# ConverterSch_2ndDriver.net
KiCad netlist of a schematic drawn in Altium Designer
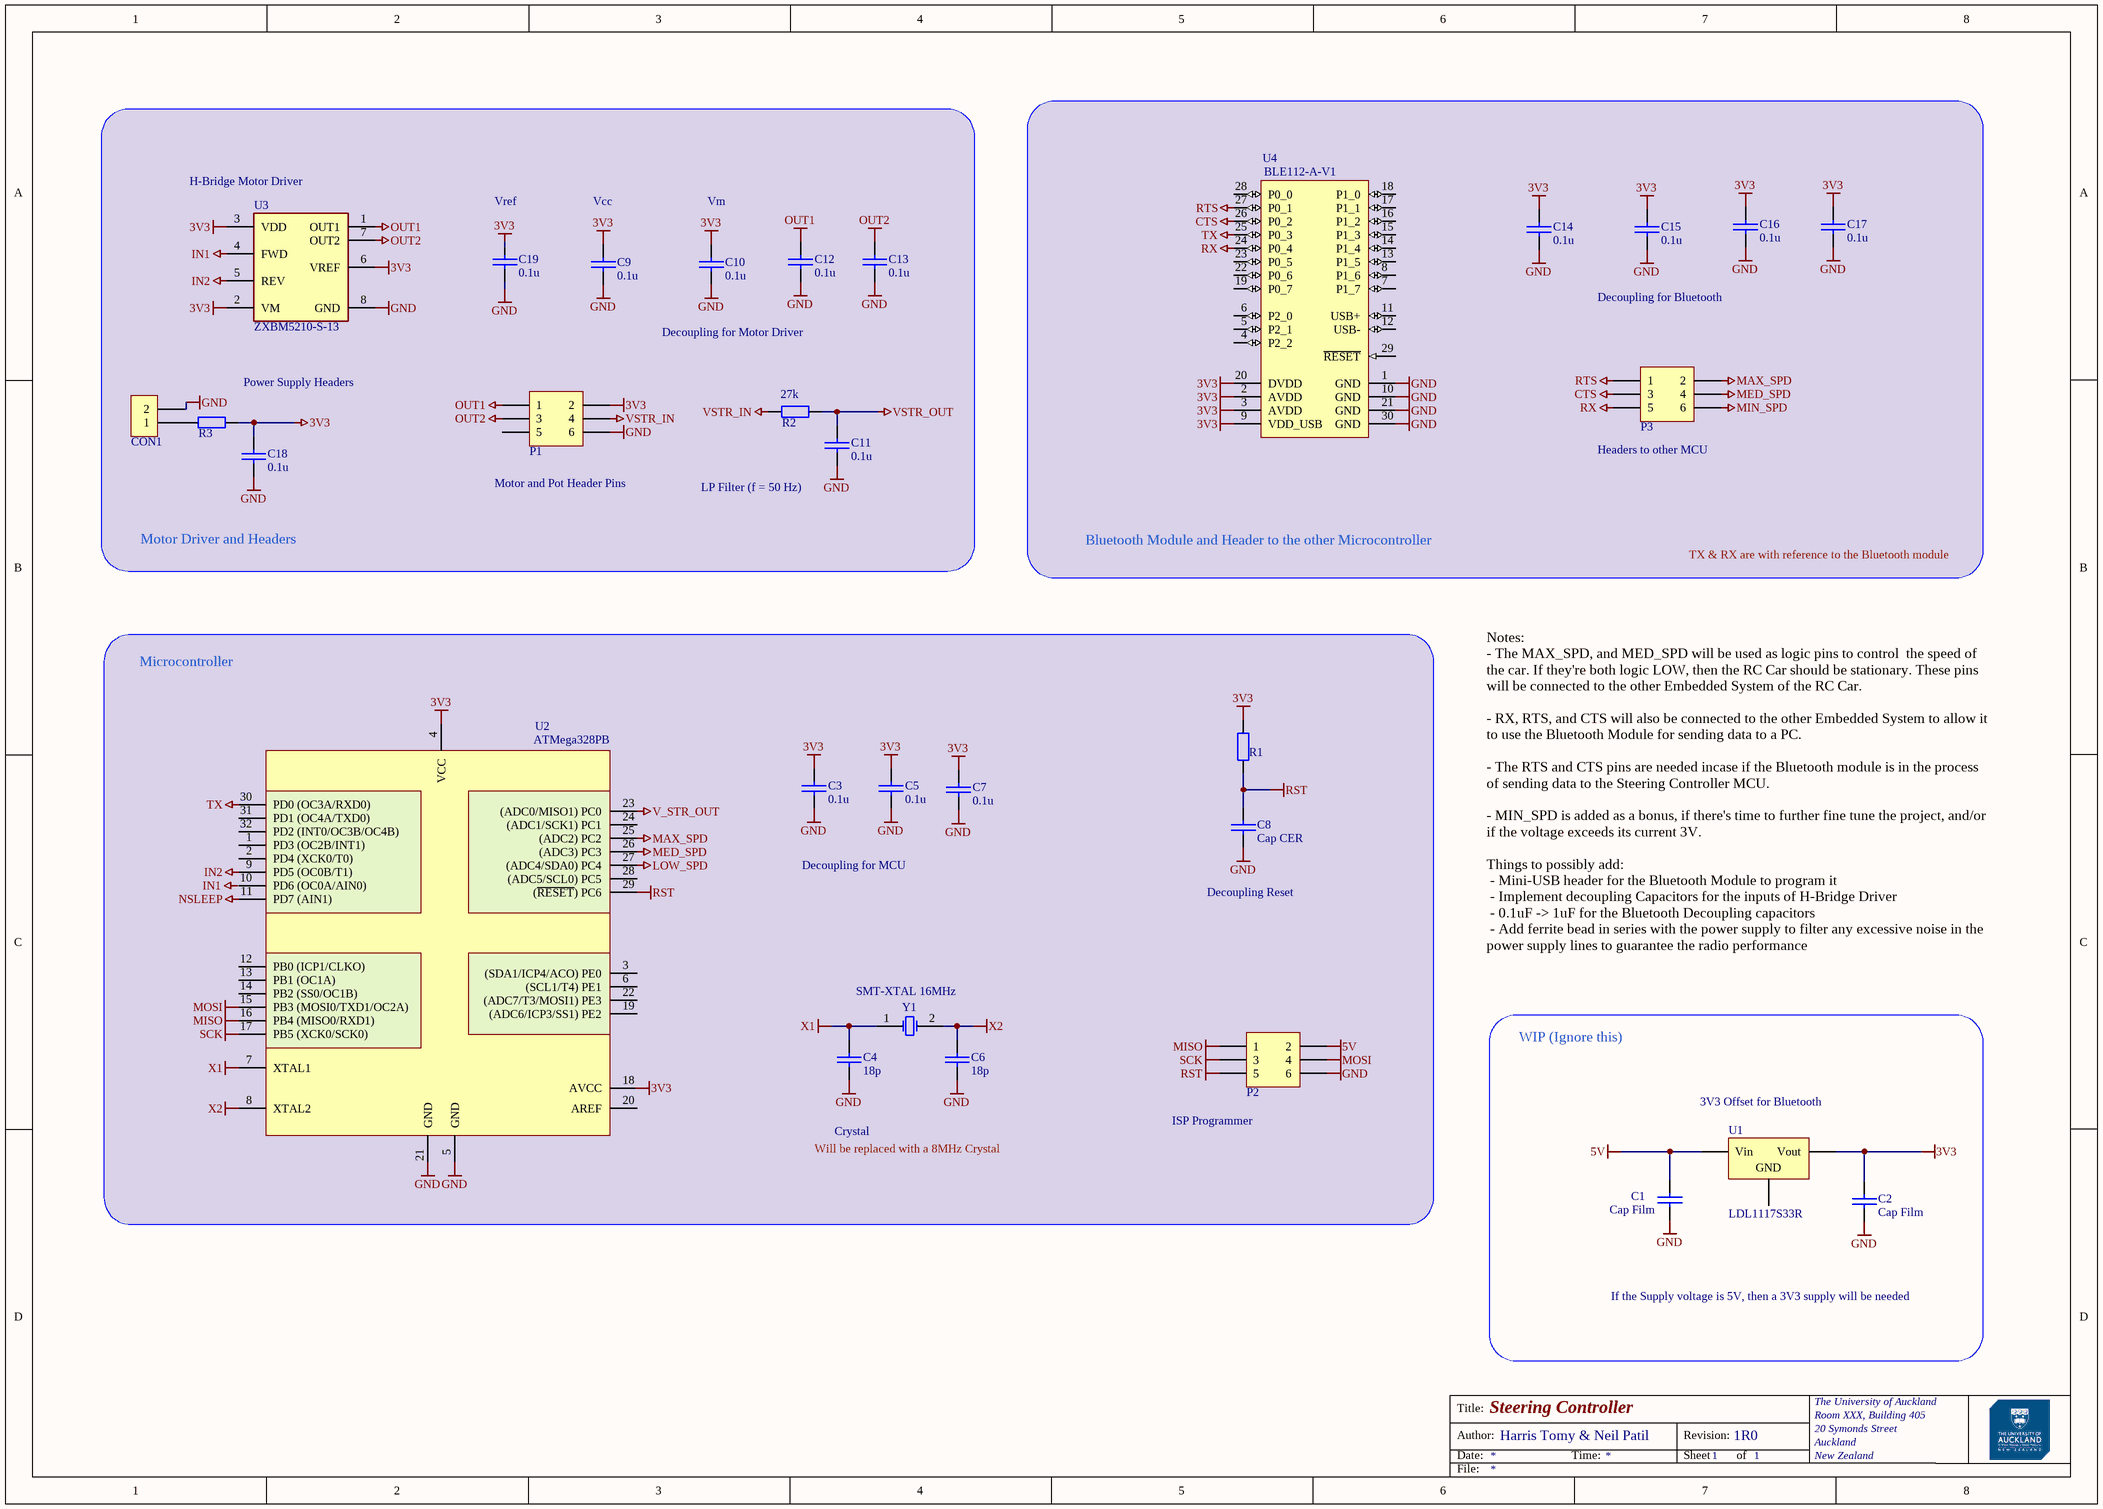
[diagram p0: ConverterSch_2ndDriver.SchDoc]

(export (version "E")
  (design (tool "Eeschema 10.0.6"))
  (components
    (comp (ref "C1")
      (value "Cap Film")
      (footprint "LDECE4150KA0N00")
      (description "CAP FILM 1.5UF 10% 50VDC 2824")
      (fields (field (name "MPN") "LDECE4150KA0N00") (field (name "MANUFACTURER") "KEMET"))
      (libsource (lib "E209_Lib") (part "Cap Film SMD LDECE4150KA0N00"))
    )
    (comp (ref "C2")
      (value "Cap Film")
      (footprint "LDECE4150KA0N00")
      (description "CAP FILM 1.5UF 10% 50VDC 2824")
      (fields (field (name "MPN") "LDECE4150KA0N00") (field (name "MANUFACTURER") "KEMET"))
      (libsource (lib "E209_Lib") (part "Cap Film SMD LDECE4150KA0N00"))
    )
    (comp (ref "C3")
      (value "0.1u")
      (footprint "C1206")
      (description "CAP CER 0.1UF 100V C0G 1206")
      (fields (field (name "MPN") "C3216C0G2A104J160AC") (field (name "MANUFACTURER") "TDK Corporation"))
      (libsource (lib "E209_Lib") (part "Cap CER Decoup C3216C0G2A104J160AC"))
    )
    (comp (ref "C4")
      (value "18p")
      (footprint "C1206")
      (description "CAP CER 0.1UF 100V C0G 1206")
      (fields (field (name "MPN") "C3216C0G2A104J160AC") (field (name "MANUFACTURER") "TDK Corporation"))
      (libsource (lib "E209_Lib") (part "Cap CER Decoup C3216C0G2A104J160AC"))
    )
    (comp (ref "C5")
      (value "0.1u")
      (footprint "C1206")
      (description "CAP CER 0.1UF 100V C0G 1206")
      (fields (field (name "MPN") "C3216C0G2A104J160AC") (field (name "MANUFACTURER") "TDK Corporation"))
      (libsource (lib "E209_Lib") (part "Cap CER Decoup C3216C0G2A104J160AC"))
    )
    (comp (ref "C6")
      (value "18p")
      (footprint "C1206")
      (description "CAP CER 0.1UF 100V C0G 1206")
      (fields (field (name "MPN") "C3216C0G2A104J160AC") (field (name "MANUFACTURER") "TDK Corporation"))
      (libsource (lib "E209_Lib") (part "Cap CER Decoup C3216C0G2A104J160AC"))
    )
    (comp (ref "C7")
      (value "0.1u")
      (footprint "C1206")
      (description "CAP CER 0.1UF 100V C0G 1206")
      (fields (field (name "MPN") "C3216C0G2A104J160AC") (field (name "MANUFACTURER") "TDK Corporation"))
      (libsource (lib "E209_Lib") (part "Cap CER Decoup C3216C0G2A104J160AC"))
    )
    (comp (ref "C8")
      (value "Cap CER")
      (footprint "C1206")
      (description "CAP CER 0.1UF 100V C0G 1206")
      (fields (field (name "MPN") "C3216C0G2A104J160AC") (field (name "MANUFACTURER") "TDK Corporation"))
      (libsource (lib "E209_Lib") (part "Cap CER Decoup C3216C0G2A104J160AC"))
    )
    (comp (ref "C9")
      (value "0.1u")
      (footprint "C1206")
      (description "CAP CER 0.1UF 100V C0G 1206")
      (fields (field (name "MPN") "C3216C0G2A104J160AC") (field (name "MANUFACTURER") "TDK Corporation"))
      (libsource (lib "E209_Lib") (part "Cap CER Decoup C3216C0G2A104J160AC"))
    )
    (comp (ref "C10")
      (value "0.1u")
      (footprint "C1206")
      (description "CAP CER 0.1UF 100V C0G 1206")
      (fields (field (name "MPN") "C3216C0G2A104J160AC") (field (name "MANUFACTURER") "TDK Corporation"))
      (libsource (lib "E209_Lib") (part "Cap CER Decoup C3216C0G2A104J160AC"))
    )
    (comp (ref "C11")
      (value "0.1u")
      (footprint "C1206")
      (description "CAP CER 0.1UF 100V C0G 1206")
      (fields (field (name "MPN") "C3216C0G2A104J160AC") (field (name "MANUFACTURER") "TDK Corporation"))
      (libsource (lib "E209_Lib") (part "Cap CER Decoup C3216C0G2A104J160AC"))
    )
    (comp (ref "C12")
      (value "0.1u")
      (footprint "C1206")
      (description "CAP CER 0.1UF 100V C0G 1206")
      (fields (field (name "MPN") "C3216C0G2A104J160AC") (field (name "MANUFACTURER") "TDK Corporation"))
      (libsource (lib "E209_Lib") (part "Cap CER Decoup C3216C0G2A104J160AC"))
    )
    (comp (ref "C13")
      (value "0.1u")
      (footprint "C1206")
      (description "CAP CER 0.1UF 100V C0G 1206")
      (fields (field (name "MPN") "C3216C0G2A104J160AC") (field (name "MANUFACTURER") "TDK Corporation"))
      (libsource (lib "E209_Lib") (part "Cap CER Decoup C3216C0G2A104J160AC"))
    )
    (comp (ref "C14")
      (value "0.1u")
      (footprint "C1206")
      (description "CAP CER 0.1UF 100V C0G 1206")
      (fields (field (name "MPN") "C3216C0G2A104J160AC") (field (name "MANUFACTURER") "TDK Corporation"))
      (libsource (lib "E209_Lib") (part "Cap CER Decoup C3216C0G2A104J160AC"))
    )
    (comp (ref "C15")
      (value "0.1u")
      (footprint "C1206")
      (description "CAP CER 0.1UF 100V C0G 1206")
      (fields (field (name "MPN") "C3216C0G2A104J160AC") (field (name "MANUFACTURER") "TDK Corporation"))
      (libsource (lib "E209_Lib") (part "Cap CER Decoup C3216C0G2A104J160AC"))
    )
    (comp (ref "C16")
      (value "0.1u")
      (footprint "C1206")
      (description "CAP CER 0.1UF 100V C0G 1206")
      (fields (field (name "MPN") "C3216C0G2A104J160AC") (field (name "MANUFACTURER") "TDK Corporation"))
      (libsource (lib "E209_Lib") (part "Cap CER Decoup C3216C0G2A104J160AC"))
    )
    (comp (ref "C17")
      (value "0.1u")
      (footprint "C1206")
      (description "CAP CER 0.1UF 100V C0G 1206")
      (fields (field (name "MPN") "C3216C0G2A104J160AC") (field (name "MANUFACTURER") "TDK Corporation"))
      (libsource (lib "E209_Lib") (part "Cap CER Decoup C3216C0G2A104J160AC"))
    )
    (comp (ref "C18")
      (value "0.1u")
      (footprint "C1206")
      (description "CAP CER 0.1UF 100V C0G 1206")
      (fields (field (name "MPN") "C3216C0G2A104J160AC") (field (name "MANUFACTURER") "TDK Corporation"))
      (libsource (lib "E209_Lib") (part "Cap CER Decoup C3216C0G2A104J160AC"))
    )
    (comp (ref "C19")
      (value "0.1u")
      (footprint "C1206")
      (description "CAP CER 0.1UF 100V C0G 1206")
      (fields (field (name "MPN") "C3216C0G2A104J160AC") (field (name "MANUFACTURER") "TDK Corporation"))
      (libsource (lib "E209_Lib") (part "Cap CER Decoup C3216C0G2A104J160AC"))
    )
    (comp (ref "CON1")
      (value "Header 2X1")
      (footprint "HDR2X1_2P54")
      (libsource (lib "CommonDevices_V1") (part "HDR2X1"))
    )
    (comp (ref "P1")
      (value "HDR3X2")
      (footprint "HDR2X3_2P54")
      (description "Header, 3-Pin, Dual row")
      (libsource (lib "CommonDevices_V1") (part "HDR3X2"))
    )
    (comp (ref "P2")
      (value "HDR3X2")
      (footprint "HDR2X3_2P54")
      (description "Header, 3-Pin, Dual row")
      (libsource (lib "CommonDevices_V1") (part "HDR3X2"))
    )
    (comp (ref "P3")
      (value "HDR3X2")
      (footprint "HDR2X3_2P54")
      (description "Header, 3-Pin, Dual row")
      (libsource (lib "CommonDevices_V1") (part "HDR3X2"))
    )
    (comp (ref "R1")
      (value "Resistor 1206")
      (footprint "R1206")
      (description "RES1206")
      (fields (field (name "MPN") "?"))
      (libsource (lib "E209_Lib") (part "RES1206"))
    )
    (comp (ref "R2")
      (value "Resistor 0805")
      (footprint "R0805")
      (description "RES0805")
      (fields (field (name "MPN") "?"))
      (libsource (lib "E209_Lib") (part "RES0805"))
    )
    (comp (ref "R3")
      (value "Resistor 0805")
      (footprint "R0805")
      (description "RES0805")
      (fields (field (name "MPN") "?"))
      (libsource (lib "E209_Lib") (part "RES0805"))
    )
    (comp (ref "U1")
      (value "LDL1117S33R")
      (footprint "SOT223L")
      (description "IC REG LINEAR 3.3V 1.2A SOT223")
      (fields (field (name "MANUFACTURER") "STMicroelectronics"))
      (libsource (lib "E209_Lib") (part "LDO LDL1117S33R"))
    )
    (comp (ref "U2")
      (value "ATMega328PB")
      (footprint "TQFP32")
      (description "IC MCU 8BIT 32KB FLASH 32TQFP")
      (libsource (lib "CommonDevices_V1") (part "ATMega328PB"))
    )
    (comp (ref "U3")
      (value "IC_Diodes_ZXBM5210-S-13_eec")
      (footprint "Diodes_ZXBM5210-S-13_0")
      (description "IC MOTOR DRIVER PWM 8SOIC")
      (fields
        (field (name "PART NUMBER") "ZXBM5210-S-13")
        (field (name "VOLTAGE") "18V")
        (field (name "MANUFACTURER") "Diodes")
      )
      (libsource (lib "ZXBM5210-S-13") (part "IC_Diodes_ZXBM5210-S-13_eec"))
    )
    (comp (ref "U4")
      (value "BLE112-A-V1")
      (footprint "BLUE-BLE112-A-V1_V")
      (libsource (lib "Integrated_Library1") (part "BLE112-A-V1"))
    )
    (comp (ref "Y1")
      (value "SMT-XTAL 16MHz")
      (footprint "HC49-US")
      (description "9C-16.000MAAJ-T crystal 16.0000MHZ 18PF SMD")
      (fields
        (field (name "MANUFACTURER") "TXC CORPORATION")
        (field (name "MANUFACTURER PART NUMBER") "9C-16.000MAAJ-T")
      )
      (libsource (lib "EE209_Library") (part "TXC9C-16_XTAL_SMT"))
    )
  )
  (nets
    (net (code "1") (name "3V3") (class "Default")
      (node (ref "C10") (pin "2") (pinfunction "2_2") (pintype "passive"))
      (node (ref "C14") (pin "2") (pinfunction "2_2") (pintype "passive"))
      (node (ref "C15") (pin "2") (pinfunction "2_2") (pintype "passive"))
      (node (ref "C16") (pin "2") (pinfunction "2_2") (pintype "passive"))
      (node (ref "C17") (pin "2") (pinfunction "2_2") (pintype "passive"))
      (node (ref "C18") (pin "2") (pinfunction "2_2") (pintype "passive"))
      (node (ref "C19") (pin "2") (pinfunction "2_2") (pintype "passive"))
      (node (ref "C2") (pin "2") (pinfunction "2_2") (pintype "passive"))
      (node (ref "C3") (pin "2") (pinfunction "2_2") (pintype "passive"))
      (node (ref "C5") (pin "2") (pinfunction "2_2") (pintype "passive"))
      (node (ref "C7") (pin "2") (pinfunction "2_2") (pintype "passive"))
      (node (ref "C9") (pin "2") (pinfunction "2_2") (pintype "passive"))
      (node (ref "P1") (pin "2") (pinfunction "2_2") (pintype "passive"))
      (node (ref "R1") (pin "1") (pinfunction "1_1") (pintype "passive"))
      (node (ref "R3") (pin "2") (pinfunction "2_2") (pintype "passive"))
      (node (ref "U1") (pin "2") (pinfunction "Vout_2") (pintype "passive"))
      (node (ref "U2") (pin "4") (pinfunction "VCC_4") (pintype "passive"))
      (node (ref "U3") (pin "2") (pinfunction "VM_2") (pintype "passive"))
      (node (ref "U3") (pin "3") (pinfunction "VDD_3") (pintype "passive"))
      (node (ref "U3") (pin "6") (pinfunction "VREF_6") (pintype "passive"))
      (node (ref "U4") (pin "2") (pinfunction "AVDD_2") (pintype "power_in"))
      (node (ref "U4") (pin "20") (pinfunction "DVDD_20") (pintype "power_in"))
      (node (ref "U4") (pin "3") (pinfunction "AVDD_3") (pintype "power_in"))
      (node (ref "U4") (pin "9") (pinfunction "VDD_USB_9") (pintype "power_in"))
    )
    (net (code "2") (name "5V") (class "Default")
      (node (ref "C1") (pin "2") (pinfunction "2_2") (pintype "passive"))
      (node (ref "P2") (pin "2") (pinfunction "2_2") (pintype "passive"))
      (node (ref "U1") (pin "3") (pinfunction "Vin_3") (pintype "passive"))
    )
    (net (code "3") (name "CTS") (class "Default")
      (node (ref "P3") (pin "3") (pinfunction "3_3") (pintype "passive"))
      (node (ref "U4") (pin "26") (pinfunction "P0_2_26") (pintype "bidirectional"))
    )
    (net (code "4") (name "GND") (class "Default")
      (node (ref "C1") (pin "1") (pinfunction "1_1") (pintype "passive"))
      (node (ref "C10") (pin "1") (pinfunction "1_1") (pintype "passive"))
      (node (ref "C11") (pin "1") (pinfunction "1_1") (pintype "passive"))
      (node (ref "C12") (pin "1") (pinfunction "1_1") (pintype "passive"))
      (node (ref "C13") (pin "1") (pinfunction "1_1") (pintype "passive"))
      (node (ref "C14") (pin "1") (pinfunction "1_1") (pintype "passive"))
      (node (ref "C15") (pin "1") (pinfunction "1_1") (pintype "passive"))
      (node (ref "C16") (pin "1") (pinfunction "1_1") (pintype "passive"))
      (node (ref "C17") (pin "1") (pinfunction "1_1") (pintype "passive"))
      (node (ref "C18") (pin "1") (pinfunction "1_1") (pintype "passive"))
      (node (ref "C19") (pin "1") (pinfunction "1_1") (pintype "passive"))
      (node (ref "C2") (pin "1") (pinfunction "1_1") (pintype "passive"))
      (node (ref "C3") (pin "1") (pinfunction "1_1") (pintype "passive"))
      (node (ref "C4") (pin "1") (pinfunction "1_1") (pintype "passive"))
      (node (ref "C5") (pin "1") (pinfunction "1_1") (pintype "passive"))
      (node (ref "C6") (pin "1") (pinfunction "1_1") (pintype "passive"))
      (node (ref "C7") (pin "1") (pinfunction "1_1") (pintype "passive"))
      (node (ref "C8") (pin "1") (pinfunction "1_1") (pintype "passive"))
      (node (ref "C9") (pin "1") (pinfunction "1_1") (pintype "passive"))
      (node (ref "CON1") (pin "2") (pinfunction "2_2") (pintype "passive"))
      (node (ref "P1") (pin "6") (pinfunction "6_6") (pintype "passive"))
      (node (ref "P2") (pin "6") (pinfunction "6_6") (pintype "passive"))
      (node (ref "U2") (pin "21") (pinfunction "GND_21") (pintype "passive"))
      (node (ref "U2") (pin "5") (pinfunction "GND_5") (pintype "passive"))
      (node (ref "U3") (pin "8") (pinfunction "GND_8") (pintype "passive"))
      (node (ref "U4") (pin "1") (pinfunction "GND_1") (pintype "power_in"))
      (node (ref "U4") (pin "10") (pinfunction "GND_10") (pintype "power_in"))
      (node (ref "U4") (pin "21") (pinfunction "GND_21") (pintype "power_in"))
      (node (ref "U4") (pin "30") (pinfunction "GND_30") (pintype "power_in"))
    )
    (net (code "5") (name "IN1") (class "Default")
      (node (ref "U3") (pin "4") (pinfunction "FWD_4") (pintype "passive"))
    )
    (net (code "6") (name "IN2") (class "Default")
      (node (ref "U2") (pin "9") (pinfunction "PD5_(OC0B/T1)_9") (pintype "passive"))
      (node (ref "U3") (pin "5") (pinfunction "REV_5") (pintype "passive"))
    )
    (net (code "7") (name "LOW_SPD") (class "Default")
      (node (ref "U2") (pin "27") (pinfunction "(ADC4/SDA0)_PC4_27") (pintype "passive"))
    )
    (net (code "8") (name "MAX_SPD") (class "Default")
      (node (ref "P3") (pin "2") (pinfunction "2_2") (pintype "passive"))
      (node (ref "U2") (pin "25") (pinfunction "(ADC2)_PC2_25") (pintype "passive"))
    )
    (net (code "9") (name "MED_SPD") (class "Default")
      (node (ref "P3") (pin "4") (pinfunction "4_4") (pintype "passive"))
      (node (ref "U2") (pin "26") (pinfunction "(ADC3)_PC3_26") (pintype "passive"))
    )
    (net (code "10") (name "MIN_SPD") (class "Default")
      (node (ref "P3") (pin "6") (pinfunction "6_6") (pintype "passive"))
    )
    (net (code "11") (name "MISO") (class "Default")
      (node (ref "P2") (pin "1") (pinfunction "1_1") (pintype "passive"))
      (node (ref "U2") (pin "16") (pinfunction "PB4_(MISO0/RXD1)_16") (pintype "passive"))
    )
    (net (code "12") (name "MOSI") (class "Default")
      (node (ref "P2") (pin "4") (pinfunction "4_4") (pintype "passive"))
      (node (ref "U2") (pin "15") (pinfunction "PB3_(MOSI0/TXD1/OC2A)_15") (pintype "passive"))
    )
    (net (code "13") (name "NSLEEP") (class "Default")
      (node (ref "U2") (pin "11") (pinfunction "PD7_(AIN1)_11") (pintype "passive"))
    )
    (net (code "14") (name "Net-(CON1-Pad1)") (class "Default")
      (node (ref "CON1") (pin "1") (pinfunction "1_1") (pintype "passive"))
      (node (ref "R3") (pin "1") (pinfunction "1_1") (pintype "passive"))
    )
    (net (code "15") (name "OUT1") (class "Default")
      (node (ref "C12") (pin "2") (pinfunction "2_2") (pintype "passive"))
      (node (ref "P1") (pin "1") (pinfunction "1_1") (pintype "passive"))
      (node (ref "U3") (pin "1") (pinfunction "OUT1_1") (pintype "passive"))
    )
    (net (code "16") (name "OUT2") (class "Default")
      (node (ref "C13") (pin "2") (pinfunction "2_2") (pintype "passive"))
      (node (ref "P1") (pin "3") (pinfunction "3_3") (pintype "passive"))
      (node (ref "U3") (pin "7") (pinfunction "OUT2_7") (pintype "passive"))
    )
    (net (code "17") (name "RST") (class "Default")
      (node (ref "C8") (pin "2") (pinfunction "2_2") (pintype "passive"))
      (node (ref "P2") (pin "5") (pinfunction "5_5") (pintype "passive"))
      (node (ref "R1") (pin "2") (pinfunction "2_2") (pintype "passive"))
      (node (ref "U2") (pin "29") (pinfunction "(~{RESET})_PC6_29") (pintype "passive"))
    )
    (net (code "18") (name "RTS") (class "Default")
      (node (ref "P3") (pin "1") (pinfunction "1_1") (pintype "passive"))
      (node (ref "U4") (pin "27") (pinfunction "P0_1_27") (pintype "bidirectional"))
    )
    (net (code "19") (name "RX") (class "Default")
      (node (ref "P3") (pin "5") (pinfunction "5_5") (pintype "passive"))
      (node (ref "U4") (pin "24") (pinfunction "P0_4_24") (pintype "bidirectional"))
    )
    (net (code "20") (name "SCK") (class "Default")
      (node (ref "P2") (pin "3") (pinfunction "3_3") (pintype "passive"))
      (node (ref "U2") (pin "17") (pinfunction "PB5_(XCK0/SCK0)_17") (pintype "passive"))
    )
    (net (code "21") (name "TX") (class "Default")
      (node (ref "U2") (pin "30") (pinfunction "PD0_(OC3A/RXD0)_30") (pintype "passive"))
      (node (ref "U4") (pin "25") (pinfunction "P0_3_25") (pintype "bidirectional"))
    )
    (net (code "22") (name "VSTR_IN") (class "Default")
      (node (ref "P1") (pin "4") (pinfunction "4_4") (pintype "passive"))
      (node (ref "R2") (pin "1") (pinfunction "1_1") (pintype "passive"))
    )
    (net (code "23") (name "VSTR_OUT") (class "Default")
      (node (ref "C11") (pin "2") (pinfunction "2_2") (pintype "passive"))
      (node (ref "R2") (pin "2") (pinfunction "2_2") (pintype "passive"))
    )
    (net (code "24") (name "V_STR_OUT") (class "Default")
      (node (ref "U2") (pin "23") (pinfunction "(ADC0/MISO1)_PC0_23") (pintype "passive"))
    )
    (net (code "25") (name "X1") (class "Default")
      (node (ref "C4") (pin "2") (pinfunction "2_2") (pintype "passive"))
      (node (ref "U2") (pin "7") (pinfunction "XTAL1_7") (pintype "passive"))
      (node (ref "Y1") (pin "1") (pinfunction "OSC1_1") (pintype "passive"))
    )
    (net (code "26") (name "X2") (class "Default")
      (node (ref "C6") (pin "2") (pinfunction "2_2") (pintype "passive"))
      (node (ref "U2") (pin "8") (pinfunction "XTAL2_8") (pintype "passive"))
      (node (ref "Y1") (pin "2") (pinfunction "OSC2_2") (pintype "passive"))
    )
    (net (code "27") (name "unconnected-(P1-Pad5)") (class "Default")
      (node (ref "P1") (pin "5") (pinfunction "5_5") (pintype "passive"))
    )
    (net (code "28") (name "unconnected-(U1-GND-Pad1)") (class "Default")
      (node (ref "U1") (pin "1") (pinfunction "GND_1") (pintype "passive"))
    )
    (net (code "29") (name "unconnected-(U2-(ADC1{slash}SCK1)_PC1-Pad24)") (class "Default")
      (node (ref "U2") (pin "24") (pinfunction "(ADC1/SCK1)_PC1_24") (pintype "passive"))
    )
    (net (code "30") (name "unconnected-(U2-(ADC5{slash}SCL0)_PC5-Pad28)") (class "Default")
      (node (ref "U2") (pin "28") (pinfunction "(ADC5/SCL0)_PC5_28") (pintype "passive"))
    )
    (net (code "31") (name "unconnected-(U2-(ADC6{slash}ICP3{slash}SS1)_PE2-Pad19)") (class "Default")
      (node (ref "U2") (pin "19") (pinfunction "(ADC6/ICP3/SS1)_PE2_19") (pintype "passive"))
    )
    (net (code "32") (name "unconnected-(U2-(ADC7{slash}T3{slash}MOSI1)_PE3-Pad22)") (class "Default")
      (node (ref "U2") (pin "22") (pinfunction "(ADC7/T3/MOSI1)_PE3_22") (pintype "passive"))
    )
    (net (code "33") (name "unconnected-(U2-(SCL1{slash}T4)_PE1-Pad6)") (class "Default")
      (node (ref "U2") (pin "6") (pinfunction "(SCL1/T4)_PE1_6") (pintype "passive"))
    )
    (net (code "34") (name "unconnected-(U2-(SDA1{slash}ICP4{slash}ACO)_PE0-Pad3)") (class "Default")
      (node (ref "U2") (pin "3") (pinfunction "(SDA1/ICP4/ACO)_PE0_3") (pintype "passive"))
    )
    (net (code "35") (name "unconnected-(U2-AREF-Pad20)") (class "Default")
      (node (ref "U2") (pin "20") (pinfunction "AREF_20") (pintype "passive"))
    )
    (net (code "36") (name "unconnected-(U2-AVCC-Pad18)") (class "Default")
      (node (ref "U2") (pin "18") (pinfunction "AVCC_18") (pintype "passive"))
    )
    (net (code "37") (name "unconnected-(U2-PB0_(ICP1{slash}CLKO)-Pad12)") (class "Default")
      (node (ref "U2") (pin "12") (pinfunction "PB0_(ICP1/CLKO)_12") (pintype "passive"))
    )
    (net (code "38") (name "unconnected-(U2-PB1_(OC1A)-Pad13)") (class "Default")
      (node (ref "U2") (pin "13") (pinfunction "PB1_(OC1A)_13") (pintype "passive"))
    )
    (net (code "39") (name "unconnected-(U2-PB2_(SS0{slash}OC1B)-Pad14)") (class "Default")
      (node (ref "U2") (pin "14") (pinfunction "PB2_(SS0/OC1B)_14") (pintype "passive"))
    )
    (net (code "40") (name "unconnected-(U2-PD1_(OC4A{slash}TXD0)-Pad31)") (class "Default")
      (node (ref "U2") (pin "31") (pinfunction "PD1_(OC4A/TXD0)_31") (pintype "passive"))
    )
    (net (code "41") (name "unconnected-(U2-PD2_(INT0{slash}OC3B{slash}OC4B)-Pad32)") (class "Default")
      (node (ref "U2") (pin "32") (pinfunction "PD2_(INT0/OC3B/OC4B)_32") (pintype "passive"))
    )
    (net (code "42") (name "unconnected-(U2-PD3_(OC2B{slash}INT1)-Pad1)") (class "Default")
      (node (ref "U2") (pin "1") (pinfunction "PD3_(OC2B/INT1)_1") (pintype "passive"))
    )
    (net (code "43") (name "unconnected-(U2-PD4_(XCK0{slash}T0)-Pad2)") (class "Default")
      (node (ref "U2") (pin "2") (pinfunction "PD4_(XCK0/T0)_2") (pintype "passive"))
    )
    (net (code "44") (name "unconnected-(U2-PD6_(OC0A{slash}AIN0)-Pad10)") (class "Default")
      (node (ref "U2") (pin "10") (pinfunction "PD6_(OC0A/AIN0)_10") (pintype "passive"))
    )
    (net (code "45") (name "unconnected-(U4-P0_0-Pad28)") (class "Default")
      (node (ref "U4") (pin "28") (pinfunction "P0_0_28") (pintype "bidirectional"))
    )
    (net (code "46") (name "unconnected-(U4-P0_5-Pad23)") (class "Default")
      (node (ref "U4") (pin "23") (pinfunction "P0_5_23") (pintype "bidirectional"))
    )
    (net (code "47") (name "unconnected-(U4-P0_6-Pad22)") (class "Default")
      (node (ref "U4") (pin "22") (pinfunction "P0_6_22") (pintype "bidirectional"))
    )
    (net (code "48") (name "unconnected-(U4-P0_7-Pad19)") (class "Default")
      (node (ref "U4") (pin "19") (pinfunction "P0_7_19") (pintype "bidirectional"))
    )
    (net (code "49") (name "unconnected-(U4-P1_0-Pad18)") (class "Default")
      (node (ref "U4") (pin "18") (pinfunction "P1_0_18") (pintype "bidirectional"))
    )
    (net (code "50") (name "unconnected-(U4-P1_1-Pad17)") (class "Default")
      (node (ref "U4") (pin "17") (pinfunction "P1_1_17") (pintype "bidirectional"))
    )
    (net (code "51") (name "unconnected-(U4-P1_2-Pad16)") (class "Default")
      (node (ref "U4") (pin "16") (pinfunction "P1_2_16") (pintype "bidirectional"))
    )
    (net (code "52") (name "unconnected-(U4-P1_3-Pad15)") (class "Default")
      (node (ref "U4") (pin "15") (pinfunction "P1_3_15") (pintype "bidirectional"))
    )
    (net (code "53") (name "unconnected-(U4-P1_4-Pad14)") (class "Default")
      (node (ref "U4") (pin "14") (pinfunction "P1_4_14") (pintype "bidirectional"))
    )
    (net (code "54") (name "unconnected-(U4-P1_5-Pad13)") (class "Default")
      (node (ref "U4") (pin "13") (pinfunction "P1_5_13") (pintype "bidirectional"))
    )
    (net (code "55") (name "unconnected-(U4-P1_6-Pad8)") (class "Default")
      (node (ref "U4") (pin "8") (pinfunction "P1_6_8") (pintype "bidirectional"))
    )
    (net (code "56") (name "unconnected-(U4-P1_7-Pad7)") (class "Default")
      (node (ref "U4") (pin "7") (pinfunction "P1_7_7") (pintype "bidirectional"))
    )
    (net (code "57") (name "unconnected-(U4-P2_0-Pad6)") (class "Default")
      (node (ref "U4") (pin "6") (pinfunction "P2_0_6") (pintype "bidirectional"))
    )
    (net (code "58") (name "unconnected-(U4-P2_1-Pad5)") (class "Default")
      (node (ref "U4") (pin "5") (pinfunction "P2_1_5") (pintype "bidirectional"))
    )
    (net (code "59") (name "unconnected-(U4-P2_2-Pad4)") (class "Default")
      (node (ref "U4") (pin "4") (pinfunction "P2_2_4") (pintype "bidirectional"))
    )
    (net (code "60") (name "unconnected-(U4-USB+-Pad11)") (class "Default")
      (node (ref "U4") (pin "11") (pinfunction "USB+_11") (pintype "bidirectional"))
    )
    (net (code "61") (name "unconnected-(U4-USB--Pad12)") (class "Default")
      (node (ref "U4") (pin "12") (pinfunction "USB-_12") (pintype "bidirectional"))
    )
    (net (code "62") (name "unconnected-(U4-~{RESET}-Pad29)") (class "Default")
      (node (ref "U4") (pin "29") (pinfunction "~{RESET}_29") (pintype "input"))
    )
  )
)
